# Pixel1_0_1.net
KiCad netlist of a schematic drawn in Altium Designer
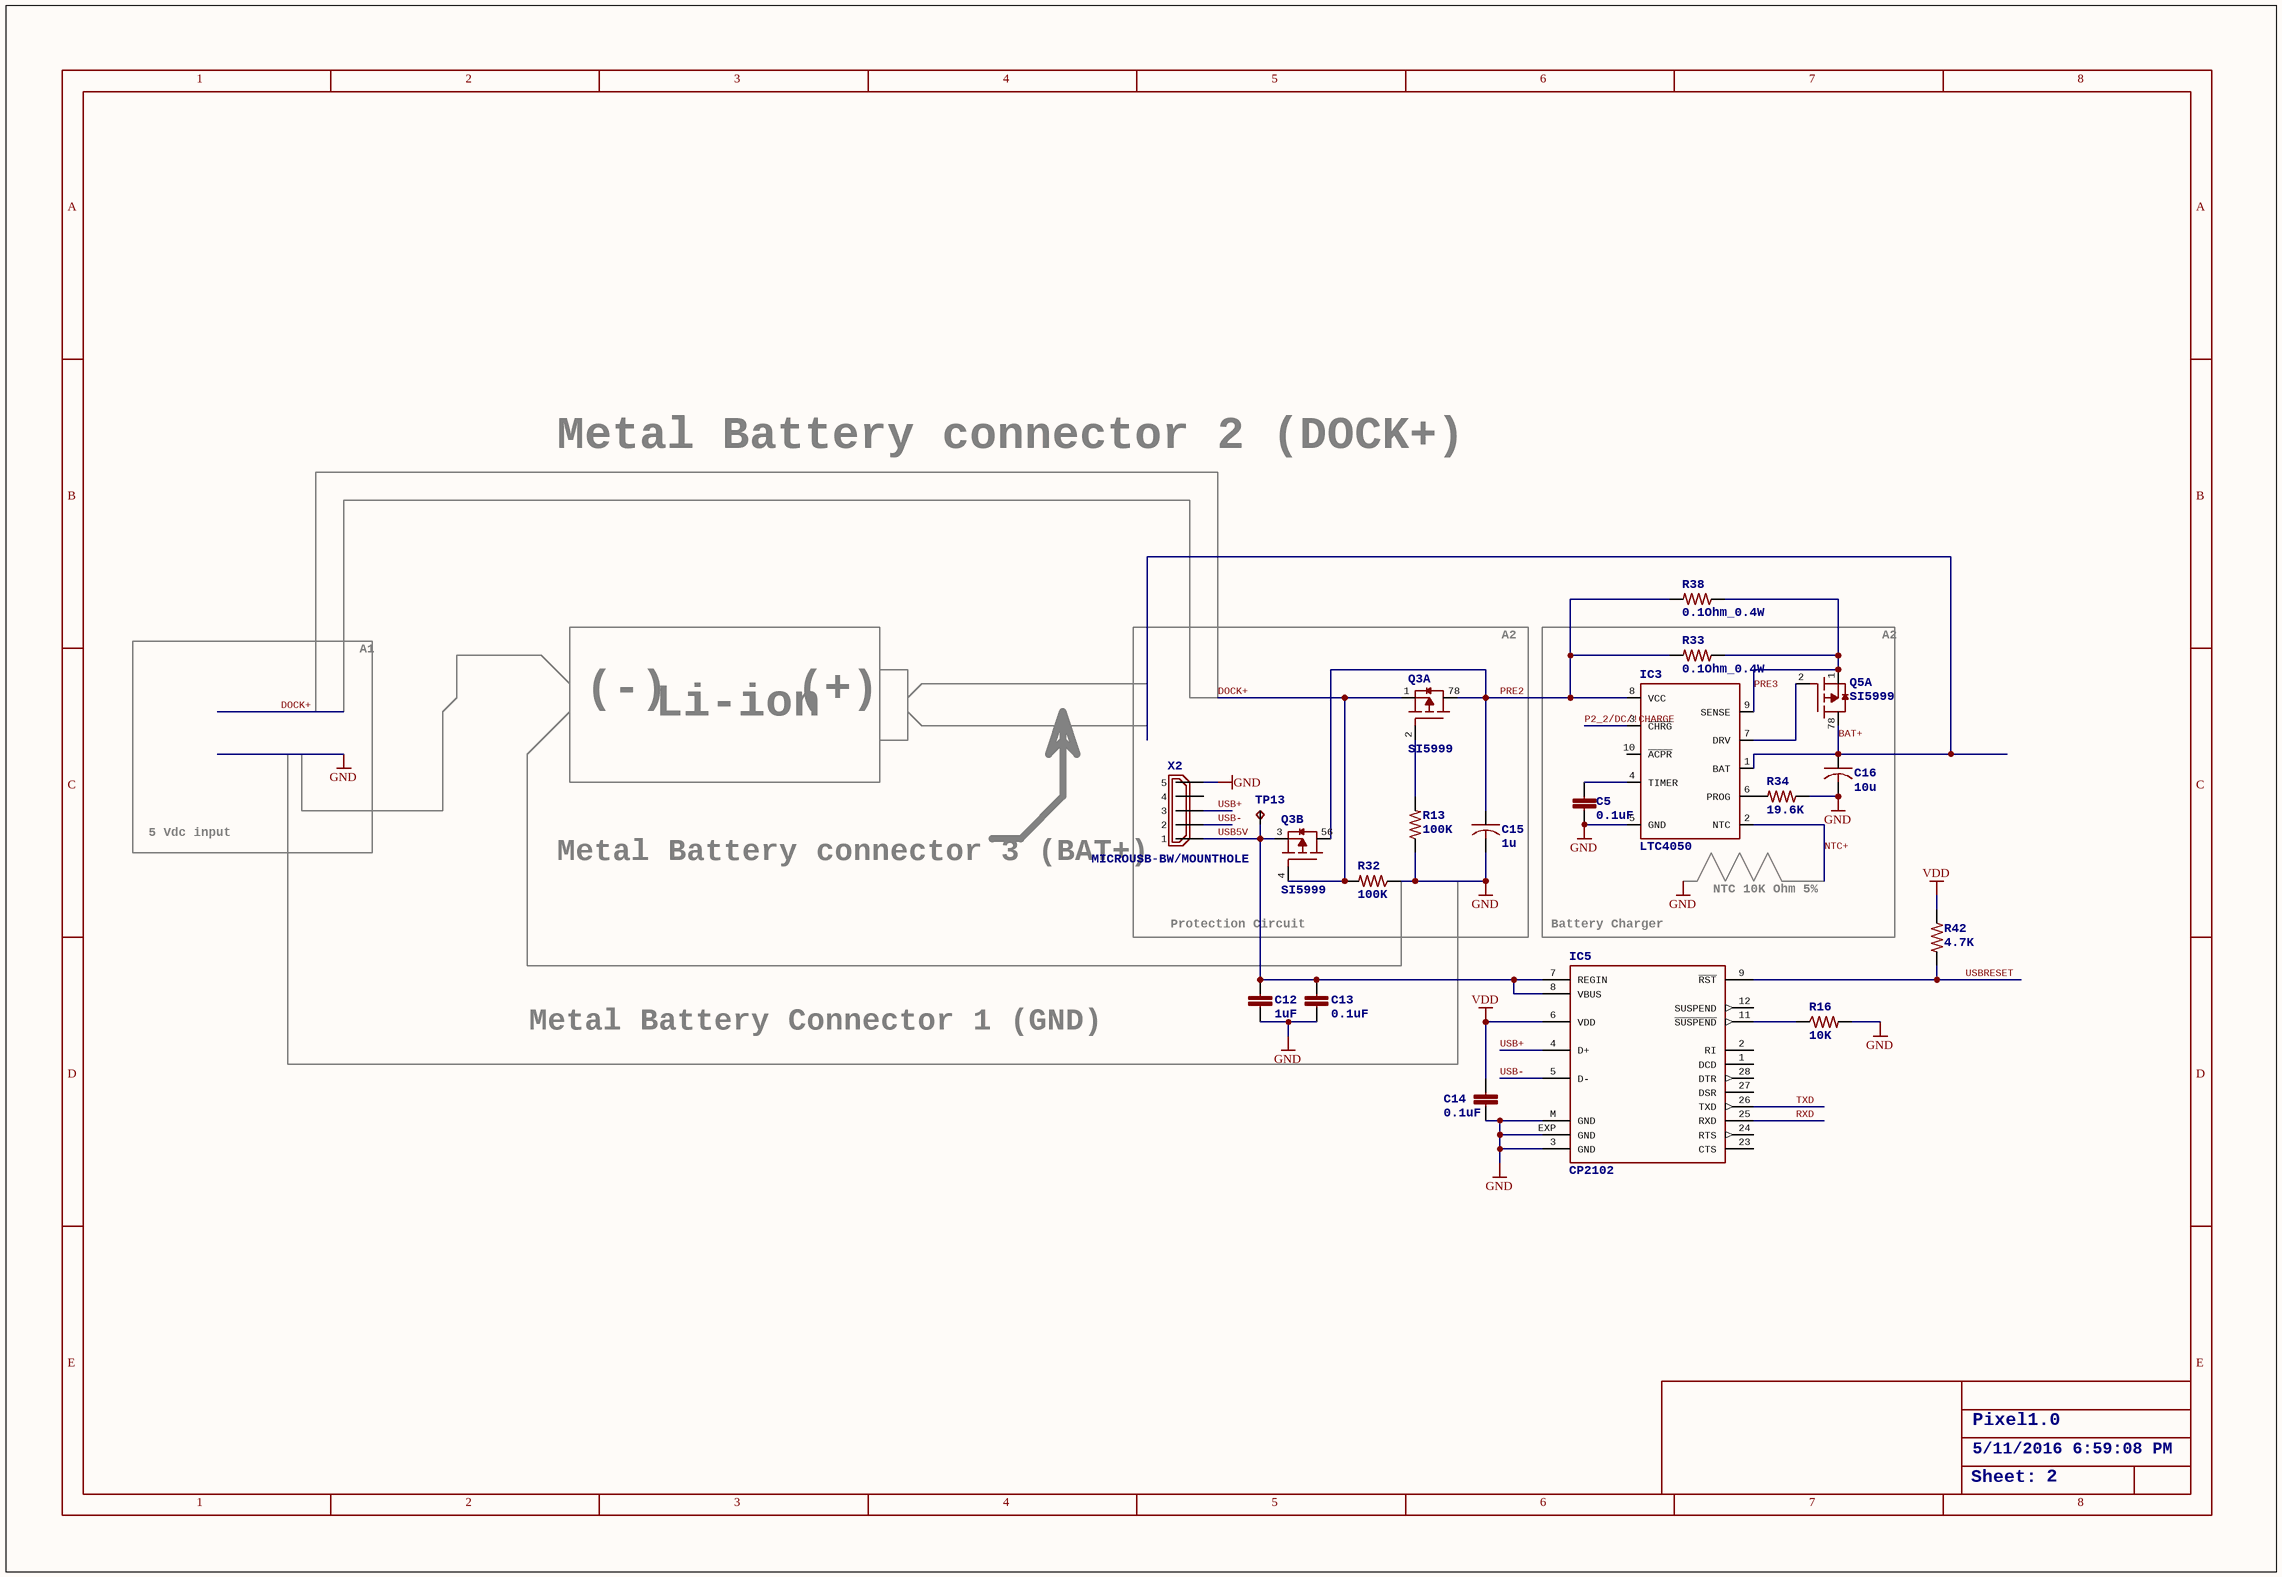
[diagram p0: Pixel1.0_1.SchDoc]

(export (version "E")
  (design (tool "Eeschema 10.0.6"))
  (components
    (comp (ref "C5")
      (value "0.1uF")
      (footprint "C0201")
      (description "CAPACITOR, European symbol")
      (libsource (lib "rcl") (part "C-EUC0201"))
    )
    (comp (ref "C12")
      (value "1uF")
      (footprint "C0201")
      (description "CAPACITOR, European symbol")
      (libsource (lib "rcl") (part "C-EUC0201"))
    )
    (comp (ref "C13")
      (value "0.1uF")
      (footprint "C0201")
      (description "CAPACITOR, European symbol")
      (libsource (lib "rcl") (part "C-EUC0201"))
    )
    (comp (ref "C14")
      (value "0.1uF")
      (footprint "C0201")
      (description "CAPACITOR, European symbol")
      (libsource (lib "rcl") (part "C-EUC0201"))
    )
    (comp (ref "C15")
      (value "1u")
      (footprint "C0201")
      (description "CAPACITOR, American symbol")
      (libsource (lib "rcl") (part "C-USC0201"))
    )
    (comp (ref "C16")
      (value "10u")
      (footprint "C0402")
      (description "CAPACITOR, American symbol")
      (libsource (lib "rcl") (part "C-USC0402"))
    )
    (comp (ref "IC3") (value "LTC4050") (footprint "MSOP10") (libsource (lib "vapeix") (part "LTC4050")))
    (comp (ref "IC5")
      (value "CP2102")
      (footprint "MLP28")
      (description "Single-Chip USB to UART Bridge   Source: www.silabs.com .. CP2101.pdf / cp2102.pdf")
      (fields (field (name "MF") "FARNELL") (field (name "MPN") "CP2102-GM"))
      (libsource (lib "silabs") (part "CP210*"))
    )
    (comp (ref "Q3")
      (value "SI5999")
      (footprint "1206-8CHIP-FET")
      (description "Dual N-Channel 30-V (D-S) MOSFET   Source: http://www.vishay.com/docs/71053/71053.pdf")
      (libsource (lib "Pixel1.0") (part "SI5999"))
    )
    (comp (ref "Q5")
      (value "SI5999")
      (footprint "1206-8CHIP-FET")
      (description "Dual N-Channel 30-V (D-S) MOSFET   Source: http://www.vishay.com/docs/71053/71053.pdf")
      (libsource (lib "Pixel1.0") (part "SI5999"))
    )
    (comp (ref "R13")
      (value "100K")
      (footprint "R0201")
      (description "RESISTOR, American symbol")
      (libsource (lib "rcl") (part "R-US_R0201"))
    )
    (comp (ref "R16")
      (value "10K")
      (footprint "R0201")
      (description "RESISTOR, American symbol")
      (libsource (lib "rcl") (part "R-US_R0201"))
    )
    (comp (ref "R32")
      (value "100K")
      (footprint "R0201")
      (description "RESISTOR, American symbol")
      (libsource (lib "rcl") (part "R-US_R0201"))
    )
    (comp (ref "R33")
      (value "0.1Ohm_0.4W")
      (footprint "R0603")
      (description "RESISTOR, American symbol")
      (libsource (lib "rcl") (part "R-US_R0603"))
    )
    (comp (ref "R34")
      (value "19.6K")
      (footprint "R0201")
      (description "RESISTOR, American symbol")
      (libsource (lib "rcl") (part "R-US_R0201"))
    )
    (comp (ref "R38")
      (value "0.1Ohm_0.4W")
      (footprint "R0603")
      (description "RESISTOR, American symbol")
      (libsource (lib "rcl") (part "R-US_R0603"))
    )
    (comp (ref "R42")
      (value "4.7K")
      (footprint "R0201")
      (description "RESISTOR, American symbol")
      (libsource (lib "rcl") (part "R-US_R0201"))
    )
    (comp (ref "TP13")
      (value "TPTP06R")
      (footprint "TP06R")
      (description "Test pad")
      (libsource (lib "testpad") (part "TPTP06R"))
    )
    (comp (ref "X2")
      (value "MICROUSB-BW/MOUNTHOLE")
      (footprint "MICRO_USB_B")
      (libsource (lib "vapeix") (part "MICROUSB-BW/MOUNTHOLE"))
    )
  )
  (nets
    (net (code "1") (name "/BAT+") (class "Default")
      (node (ref "C16") (pin "1") (pinfunction "1_1") (pintype "passive"))
      (node (ref "IC3") (pin "1") (pinfunction "BAT_1") (pintype "passive"))
      (node (ref "Q5") (pin "78") (pinfunction "D1_78") (pintype "passive"))
    )
    (net (code "2") (name "/DOCK+") (class "Default")
      (node (ref "Q3") (pin "1") (pinfunction "S1_1") (pintype "passive"))
      (node (ref "Q3") (pin "4") (pinfunction "G2_4") (pintype "passive"))
      (node (ref "R32") (pin "2") (pinfunction "2_2") (pintype "passive"))
    )
    (net (code "3") (name "/NTC+") (class "Default")
      (node (ref "IC3") (pin "2") (pinfunction "NTC_2") (pintype "passive"))
    )
    (net (code "4") (name "/P2_2{slash}DC{slash}!CHARGE") (class "Default")
      (node (ref "IC3") (pin "3") (pinfunction "~{CHRG}_3") (pintype "open_collector"))
    )
    (net (code "5") (name "/PRE2") (class "Default")
      (node (ref "C15") (pin "1") (pinfunction "1_1") (pintype "passive"))
      (node (ref "IC3") (pin "8") (pinfunction "VCC_8") (pintype "power_in"))
      (node (ref "Q3") (pin "56") (pinfunction "D2_56") (pintype "passive"))
      (node (ref "Q3") (pin "78") (pinfunction "D1_78") (pintype "passive"))
      (node (ref "R33") (pin "2") (pinfunction "2_2") (pintype "passive"))
      (node (ref "R38") (pin "2") (pinfunction "2_2") (pintype "passive"))
    )
    (net (code "6") (name "/PRE3") (class "Default")
      (node (ref "IC3") (pin "9") (pinfunction "SENSE_9") (pintype "open_collector"))
      (node (ref "Q5") (pin "1") (pinfunction "S1_1") (pintype "passive"))
      (node (ref "R33") (pin "1") (pinfunction "1_1") (pintype "passive"))
      (node (ref "R38") (pin "1") (pinfunction "1_1") (pintype "passive"))
    )
    (net (code "7") (name "/RXD") (class "Default")
      (node (ref "IC5") (pin "25") (pinfunction "RXD_25") (pintype "passive"))
    )
    (net (code "8") (name "/TXD") (class "Default")
      (node (ref "IC5") (pin "26") (pinfunction "TXD_26") (pintype "output"))
    )
    (net (code "9") (name "/USB+") (class "Default")
      (node (ref "IC5") (pin "4") (pinfunction "D+_4") (pintype "passive"))
      (node (ref "X2") (pin "P$3") (pinfunction "3_P$3") (pintype "passive"))
    )
    (net (code "10") (name "/USB-") (class "Default")
      (node (ref "IC5") (pin "5") (pinfunction "D-_5") (pintype "passive"))
      (node (ref "X2") (pin "P$2") (pinfunction "2_P$2") (pintype "passive"))
    )
    (net (code "11") (name "/USB5V") (class "Default")
      (node (ref "C12") (pin "1") (pinfunction "1_1") (pintype "passive"))
      (node (ref "C13") (pin "1") (pinfunction "1_1") (pintype "passive"))
      (node (ref "IC5") (pin "7") (pinfunction "REGIN_7") (pintype "passive"))
      (node (ref "IC5") (pin "8") (pinfunction "VBUS_8") (pintype "passive"))
      (node (ref "Q3") (pin "3") (pinfunction "S2_3") (pintype "passive"))
      (node (ref "TP13") (pin "TP") (pinfunction "TP_TP") (pintype "passive"))
      (node (ref "X2") (pin "P$1") (pinfunction "1_P$1") (pintype "passive"))
    )
    (net (code "12") (name "/USBRESET") (class "Default")
      (node (ref "IC5") (pin "9") (pinfunction "~{RST}_9") (pintype "passive"))
      (node (ref "R42") (pin "2") (pinfunction "2_2") (pintype "passive"))
    )
    (net (code "13") (name "GND") (class "Default")
      (node (ref "C12") (pin "2") (pinfunction "2_2") (pintype "passive"))
      (node (ref "C13") (pin "2") (pinfunction "2_2") (pintype "passive"))
      (node (ref "C14") (pin "2") (pinfunction "2_2") (pintype "passive"))
      (node (ref "C15") (pin "2") (pinfunction "2_2") (pintype "passive"))
      (node (ref "C16") (pin "2") (pinfunction "2_2") (pintype "passive"))
      (node (ref "C5") (pin "2") (pinfunction "2_2") (pintype "passive"))
      (node (ref "IC3") (pin "5") (pinfunction "GND_5") (pintype "power_in"))
      (node (ref "IC5") (pin "3") (pinfunction "GND_3") (pintype "power_in"))
      (node (ref "IC5") (pin "EXP") (pinfunction "GND_EXP") (pintype "power_in"))
      (node (ref "IC5") (pin "M") (pinfunction "GND_M") (pintype "power_in"))
      (node (ref "R13") (pin "1") (pinfunction "1_1") (pintype "passive"))
      (node (ref "R16") (pin "2") (pinfunction "2_2") (pintype "passive"))
      (node (ref "R32") (pin "1") (pinfunction "1_1") (pintype "passive"))
      (node (ref "R34") (pin "1") (pinfunction "1_1") (pintype "passive"))
      (node (ref "X2") (pin "P$5") (pinfunction "5_P$5") (pintype "passive"))
    )
    (net (code "14") (name "Net-(IC3-DRV)") (class "Default")
      (node (ref "IC3") (pin "7") (pinfunction "DRV_7") (pintype "passive"))
      (node (ref "Q5") (pin "2") (pinfunction "G1_2") (pintype "passive"))
    )
    (net (code "15") (name "Net-(IC3-PROG)") (class "Default")
      (node (ref "IC3") (pin "6") (pinfunction "PROG_6") (pintype "passive"))
      (node (ref "R34") (pin "2") (pinfunction "2_2") (pintype "passive"))
    )
    (net (code "16") (name "Net-(IC3-TIMER)") (class "Default")
      (node (ref "C5") (pin "1") (pinfunction "1_1") (pintype "passive"))
      (node (ref "IC3") (pin "4") (pinfunction "TIMER_4") (pintype "passive"))
    )
    (net (code "17") (name "Net-(IC5-~{SUSPEND})") (class "Default")
      (node (ref "IC5") (pin "11") (pinfunction "~{SUSPEND}_11") (pintype "output"))
      (node (ref "R16") (pin "1") (pinfunction "1_1") (pintype "passive"))
    )
    (net (code "18") (name "Net-(Q3A-G1)") (class "Default")
      (node (ref "Q3") (pin "2") (pinfunction "G1_2") (pintype "passive"))
      (node (ref "R13") (pin "2") (pinfunction "2_2") (pintype "passive"))
    )
    (net (code "19") (name "VDD") (class "Default")
      (node (ref "C14") (pin "1") (pinfunction "1_1") (pintype "passive"))
      (node (ref "IC5") (pin "6") (pinfunction "VDD_6") (pintype "power_in"))
      (node (ref "R42") (pin "1") (pinfunction "1_1") (pintype "passive"))
    )
    (net (code "20") (name "unconnected-(IC3-~{ACPR}-Pad10)") (class "Default")
      (node (ref "IC3") (pin "10") (pinfunction "~{ACPR}_10") (pintype "passive"))
    )
    (net (code "21") (name "unconnected-(IC5-CTS-Pad23)") (class "Default")
      (node (ref "IC5") (pin "23") (pinfunction "CTS_23") (pintype "passive"))
    )
    (net (code "22") (name "unconnected-(IC5-DCD-Pad1)") (class "Default")
      (node (ref "IC5") (pin "1") (pinfunction "DCD_1") (pintype "passive"))
    )
    (net (code "23") (name "unconnected-(IC5-DSR-Pad27)") (class "Default")
      (node (ref "IC5") (pin "27") (pinfunction "DSR_27") (pintype "passive"))
    )
    (net (code "24") (name "unconnected-(IC5-DTR-Pad28)") (class "Default")
      (node (ref "IC5") (pin "28") (pinfunction "DTR_28") (pintype "output"))
    )
    (net (code "25") (name "unconnected-(IC5-RI-Pad2)") (class "Default")
      (node (ref "IC5") (pin "2") (pinfunction "RI_2") (pintype "passive"))
    )
    (net (code "26") (name "unconnected-(IC5-RTS-Pad24)") (class "Default")
      (node (ref "IC5") (pin "24") (pinfunction "RTS_24") (pintype "output"))
    )
    (net (code "27") (name "unconnected-(IC5-SUSPEND-Pad12)") (class "Default")
      (node (ref "IC5") (pin "12") (pinfunction "SUSPEND_12") (pintype "output"))
    )
    (net (code "28") (name "unconnected-(X2-4-PadP$4)") (class "Default")
      (node (ref "X2") (pin "P$4") (pinfunction "4_P$4") (pintype "passive"))
    )
  )
)
